# SCH_ThePoweredProject_2023-10-22.net
KiCad netlist of a schematic drawn in EasyEDA
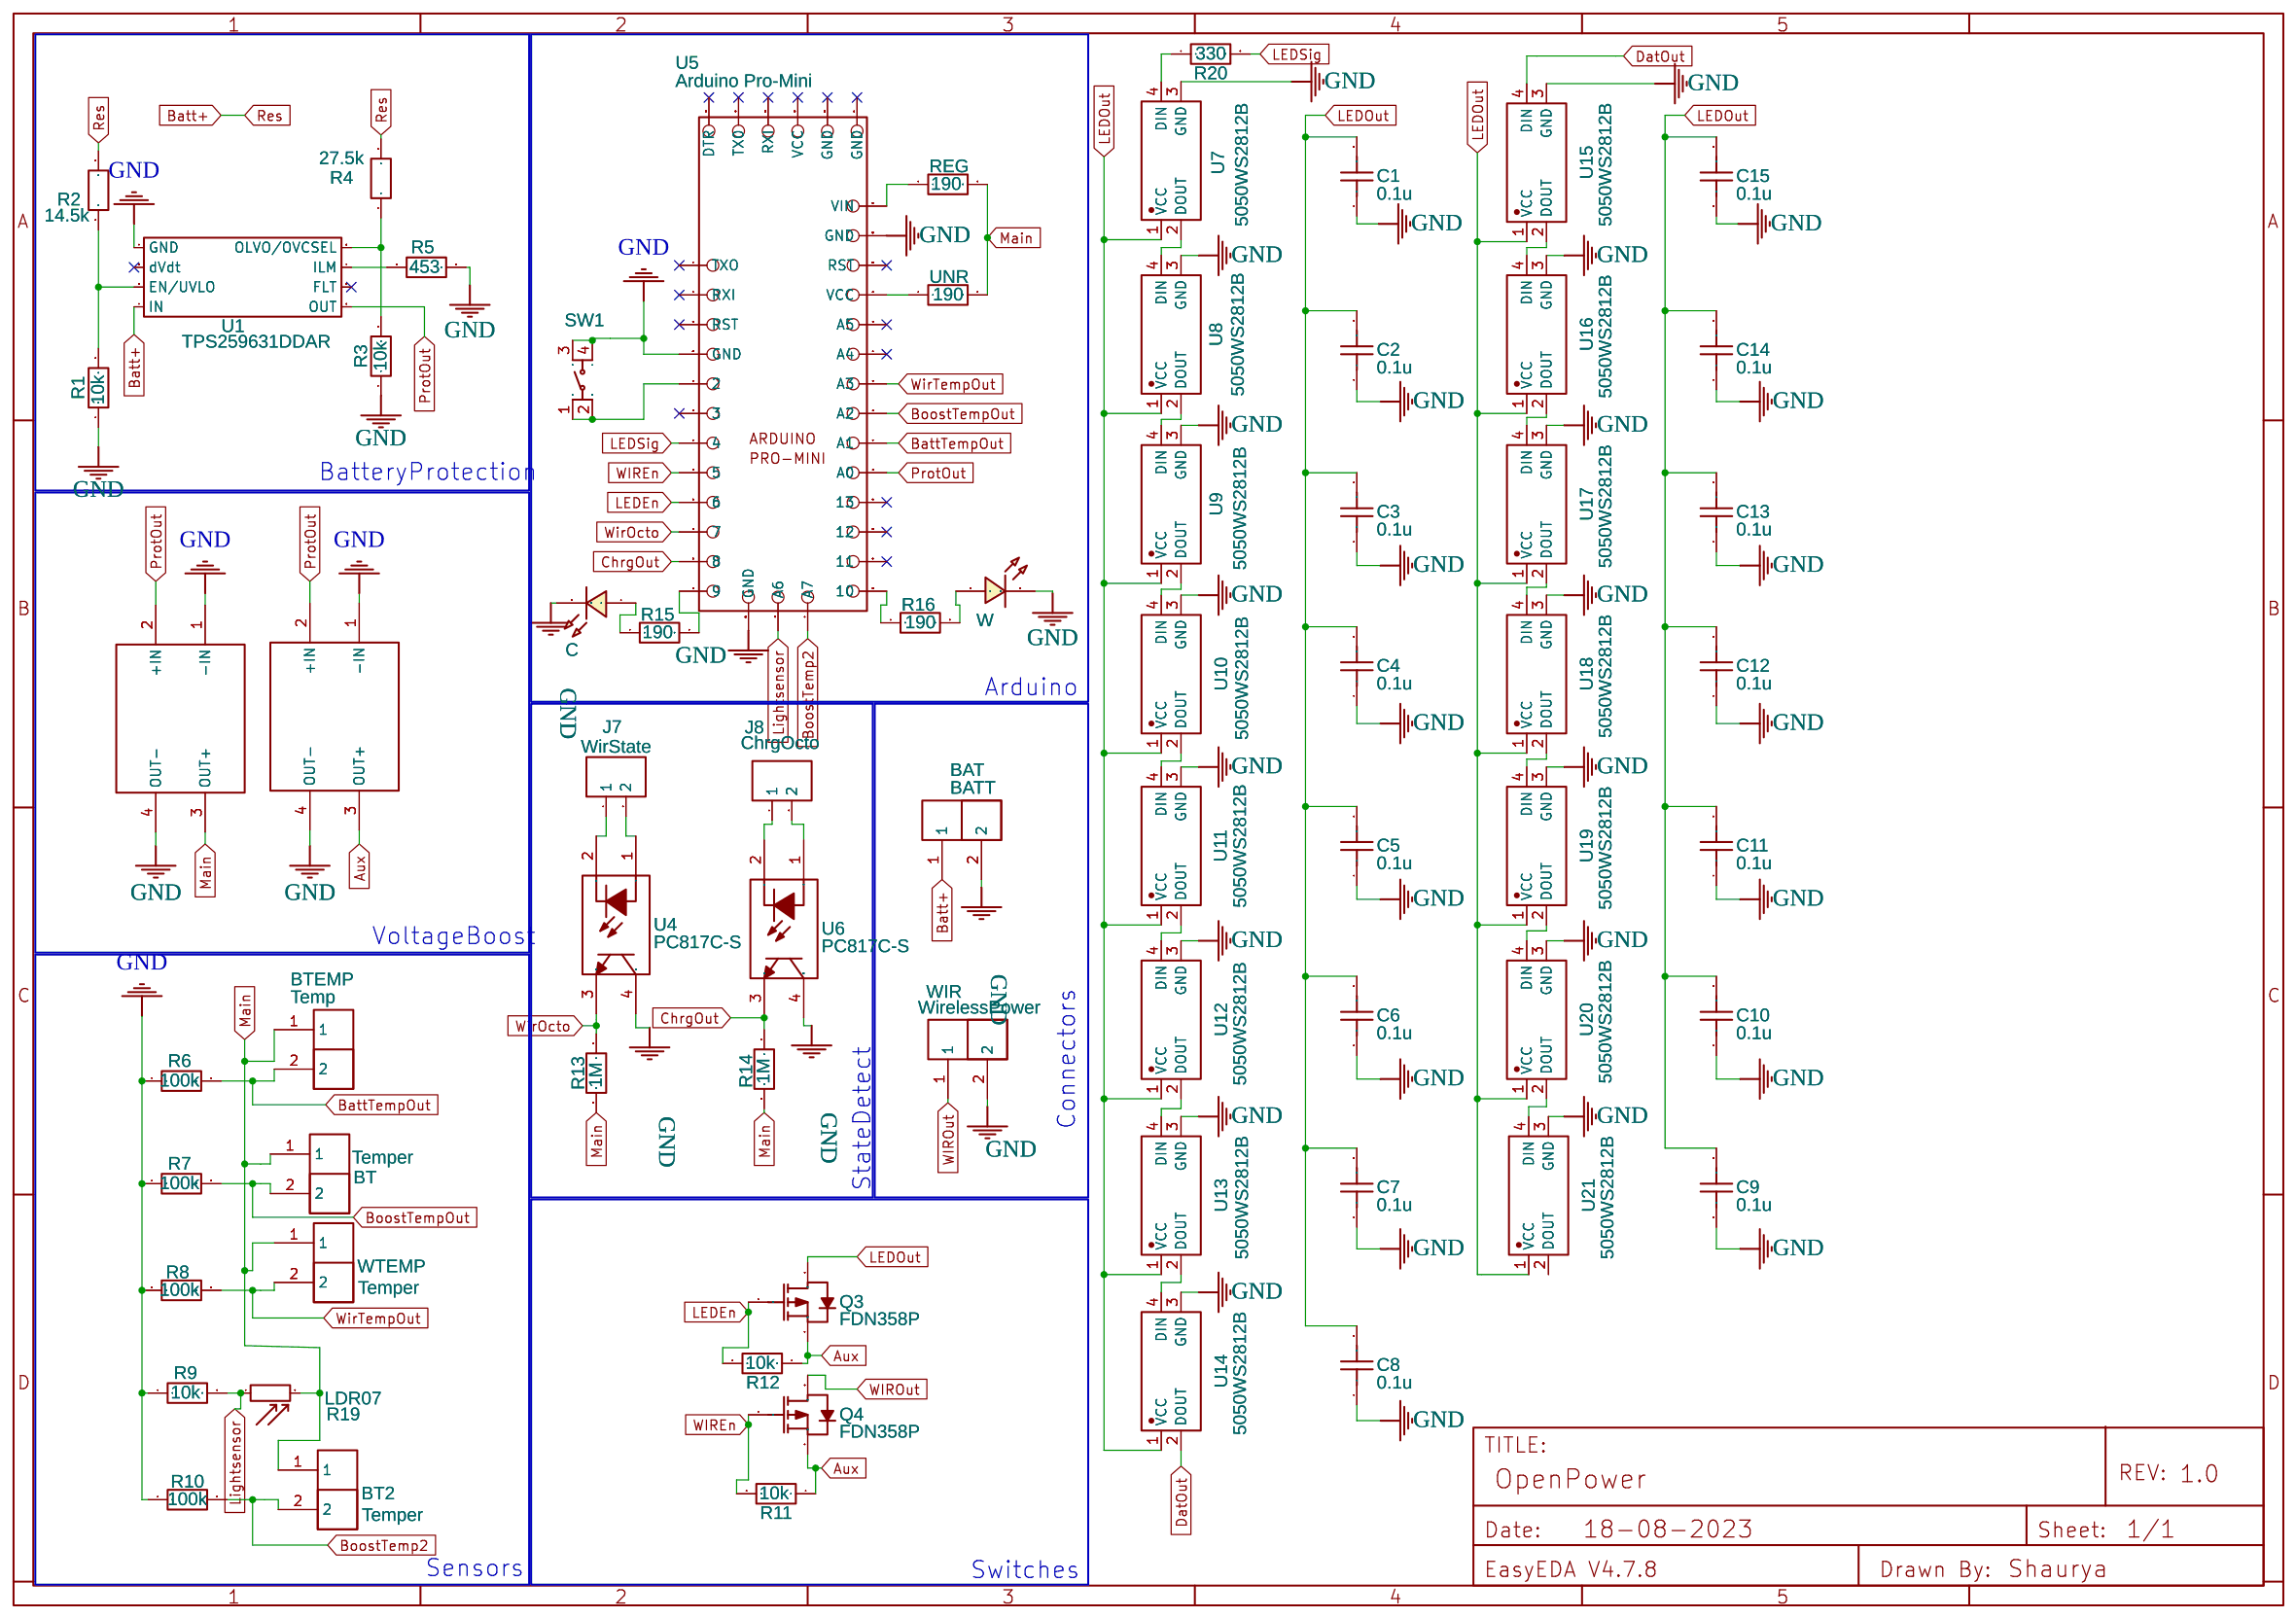
[diagram p0: schematic sheet]

(export (version "E")
  (design (tool "Eeschema 10.0.6"))
  (components
    (comp (ref "BAT") (value "BATT") (libsource (lib "") (part "2 smd pads")))
    (comp (ref "BT") (value "Temper") (libsource (lib "") (part "2 smd pads_4")))
    (comp (ref "BT2") (value "Temper") (libsource (lib "") (part "2 smd pads_4")))
    (comp (ref "BTEMP") (value "Temp") (libsource (lib "") (part "2 smd pads_1")))
    (comp (ref "C")
      (value "LED2")
      (fields
        (field (name "Manufacturer Part") "19-217/R6C-AL1M2VY/3T")
        (field (name "Manufacturer") "EVERLIGHT(台湾亿光)")
      )
      (libsource (lib "") (part "LED-0603_R"))
    )
    (comp (ref "C1") (value "0.1u") (libsource (lib "") (part "C_0603_US")))
    (comp (ref "C2") (value "0.1u") (libsource (lib "") (part "C_0603_US")))
    (comp (ref "C3") (value "0.1u") (libsource (lib "") (part "C_0603_US")))
    (comp (ref "C4") (value "0.1u") (libsource (lib "") (part "C_0603_US")))
    (comp (ref "C5") (value "0.1u") (libsource (lib "") (part "C_0603_US")))
    (comp (ref "C6") (value "0.1u") (libsource (lib "") (part "C_0603_US")))
    (comp (ref "C7") (value "0.1u") (libsource (lib "") (part "C_0603_US")))
    (comp (ref "C8") (value "0.1u") (libsource (lib "") (part "C_0603_US")))
    (comp (ref "C9") (value "0.1u") (libsource (lib "") (part "C_0603_US")))
    (comp (ref "C10") (value "0.1u") (libsource (lib "") (part "C_0603_US")))
    (comp (ref "C11") (value "0.1u") (libsource (lib "") (part "C_0603_US")))
    (comp (ref "C12") (value "0.1u") (libsource (lib "") (part "C_0603_US")))
    (comp (ref "C13") (value "0.1u") (libsource (lib "") (part "C_0603_US")))
    (comp (ref "C14") (value "0.1u") (libsource (lib "") (part "C_0603_US")))
    (comp (ref "C15") (value "0.1u") (libsource (lib "") (part "C_0603_US")))
    (comp (ref "J7") (value "WirState") (libsource (lib "") (part "HDR-M-2.54_1x2")))
    (comp (ref "J8") (value "ChrgOcto") (libsource (lib "") (part "HDR-M-2.54_1x2")))
    (comp (ref "Q3")
      (value "FDN358P")
      (fields (field (name "Manufacturer") "onsemi(安森美)"))
      (libsource (lib "") (part "FDN358P"))
    )
    (comp (ref "Q4")
      (value "FDN358P")
      (fields (field (name "Manufacturer") "onsemi(安森美)"))
      (libsource (lib "") (part "FDN358P"))
    )
    (comp (ref "R1") (value "10k") (libsource (lib "") (part "R_0603_EU_4")))
    (comp (ref "R2") (value "14.5k") (libsource (lib "") (part "R_0603_EU_4")))
    (comp (ref "R3") (value "10k") (libsource (lib "") (part "R_0603_EU_4")))
    (comp (ref "R4") (value "27.5k") (libsource (lib "") (part "R_0603_EU_4")))
    (comp (ref "R5") (value "453") (libsource (lib "") (part "R_0603_EU_2")))
    (comp (ref "R6") (value "100k") (libsource (lib "") (part "R_0603_EU_1")))
    (comp (ref "R7") (value "100k") (libsource (lib "") (part "R_0603_EU_1")))
    (comp (ref "R8") (value "100k") (libsource (lib "") (part "R_0603_EU_1")))
    (comp (ref "R9") (value "10k") (libsource (lib "") (part "R_0603_EU_1")))
    (comp (ref "R10") (value "100k") (libsource (lib "") (part "R_0603_EU_1")))
    (comp (ref "R11") (value "10k") (libsource (lib "") (part "R_0603_EU_2")))
    (comp (ref "R12") (value "10k") (libsource (lib "") (part "R_0603_EU_2")))
    (comp (ref "R13") (value "1M") (libsource (lib "") (part "R_0603_EU")))
    (comp (ref "R14") (value "1M") (libsource (lib "") (part "R_0603_EU")))
    (comp (ref "R15") (value "190") (libsource (lib "") (part "R_0603_EU_1")))
    (comp (ref "R16") (value "190") (libsource (lib "") (part "R_0603_EU_1")))
    (comp (ref "R19") (value "LDR07") (libsource (lib "") (part "LDR07")))
    (comp (ref "R20") (value "330") (libsource (lib "") (part "R_0603_EU_1")))
    (comp (ref "REG") (value "190") (libsource (lib "") (part "R_0603_EU_3")))
    (comp (ref "SW1")
      (value "Black SMD switch")
      (fields (field (name "Manufacturer Part") "PTS 647 SM50 SMTR2 LFS") (field (name "Manufacturer") "C&K"))
      (libsource (lib "") (part "Black SMD switch"))
    )
    (comp (ref "U1") (value "TPS259631DDAR") (libsource (lib "") (part "TPS259631DDAR")))
    (comp (ref "U2")
      (value "Mini boost DC-DC converter")
      (libsource (lib "") (part "Mini boost DC-DC converter"))
    )
    (comp (ref "U3")
      (value "Mini boost DC-DC converter")
      (libsource (lib "") (part "Mini boost DC-DC converter"))
    )
    (comp (ref "U4")
      (value "PC817C-S")
      (fields (field (name "Manufacturer") "UMW(广东友台半导体)"))
      (libsource (lib "") (part "PC817C-S"))
    )
    (comp (ref "U5") (value "Arduino Pro-Mini") (libsource (lib "") (part "Arduino Pro-Mini")))
    (comp (ref "U6")
      (value "PC817C-S")
      (fields (field (name "Manufacturer") "UMW(广东友台半导体)"))
      (libsource (lib "") (part "PC817C-S"))
    )
    (comp (ref "U7") (value "5050WS2812B") (libsource (lib "") (part "5050WS2812B")))
    (comp (ref "U8") (value "5050WS2812B") (libsource (lib "") (part "5050WS2812B")))
    (comp (ref "U9") (value "5050WS2812B") (libsource (lib "") (part "5050WS2812B")))
    (comp (ref "U10") (value "5050WS2812B") (libsource (lib "") (part "5050WS2812B")))
    (comp (ref "U11") (value "5050WS2812B") (libsource (lib "") (part "5050WS2812B")))
    (comp (ref "U12") (value "5050WS2812B") (libsource (lib "") (part "5050WS2812B")))
    (comp (ref "U13") (value "5050WS2812B") (libsource (lib "") (part "5050WS2812B")))
    (comp (ref "U14") (value "5050WS2812B") (libsource (lib "") (part "5050WS2812B")))
    (comp (ref "U15") (value "5050WS2812B") (libsource (lib "") (part "5050WS2812B")))
    (comp (ref "U16") (value "5050WS2812B") (libsource (lib "") (part "5050WS2812B")))
    (comp (ref "U17") (value "5050WS2812B") (libsource (lib "") (part "5050WS2812B")))
    (comp (ref "U18") (value "5050WS2812B") (libsource (lib "") (part "5050WS2812B")))
    (comp (ref "U19") (value "5050WS2812B") (libsource (lib "") (part "5050WS2812B")))
    (comp (ref "U20") (value "5050WS2812B") (libsource (lib "") (part "5050WS2812B")))
    (comp (ref "U21") (value "5050WS2812B") (libsource (lib "") (part "5050WS2812B")))
    (comp (ref "UNR") (value "190") (libsource (lib "") (part "R_0603_EU_5")))
    (comp (ref "W")
      (value "Led1")
      (fields
        (field (name "Manufacturer Part") "19-217/R6C-AL1M2VY/3T")
        (field (name "Manufacturer") "EVERLIGHT(台湾亿光)")
      )
      (libsource (lib "") (part "LED-0603_R_1"))
    )
    (comp (ref "WIR") (value "WirelessPower") (libsource (lib "") (part "2 smd pads_2")))
    (comp (ref "WTEMP") (value "Temper") (libsource (lib "") (part "2 smd pads_3")))
  )
  (nets
    (net (code "1") (name "Aux") (class "Default")
      (node (ref "Q3") (pin "2") (pinfunction "S_2") (pintype "unspecified"))
      (node (ref "Q4") (pin "2") (pinfunction "S_2") (pintype "unspecified"))
      (node (ref "R11") (pin "1") (pinfunction "1_1") (pintype "unspecified"))
      (node (ref "R12") (pin "1") (pinfunction "1_1") (pintype "unspecified"))
      (node (ref "U3") (pin "3") (pinfunction "OUT+_3") (pintype "unspecified"))
    )
    (net (code "2") (name "Batt+") (class "Default")
      (node (ref "BAT") (pin "1") (pinfunction "1_1") (pintype "unspecified"))
      (node (ref "R2") (pin "2") (pinfunction "2_2") (pintype "unspecified"))
      (node (ref "R4") (pin "2") (pinfunction "2_2") (pintype "unspecified"))
      (node (ref "U1") (pin "4") (pinfunction "IN_4") (pintype "unspecified"))
    )
    (net (code "3") (name "BattTempOut") (class "Default")
      (node (ref "BTEMP") (pin "2") (pinfunction "2_2") (pintype "unspecified"))
      (node (ref "R6") (pin "2") (pinfunction "2_2") (pintype "unspecified"))
      (node (ref "U5") (pin "A1") (pinfunction "A1_A1") (pintype "unspecified"))
    )
    (net (code "4") (name "BoostTemp2") (class "Default")
      (node (ref "BT2") (pin "2") (pinfunction "2_2") (pintype "unspecified"))
      (node (ref "R10") (pin "2") (pinfunction "2_2") (pintype "unspecified"))
      (node (ref "U5") (pin "A7") (pinfunction "A7_A7") (pintype "unspecified"))
    )
    (net (code "5") (name "BoostTempOut") (class "Default")
      (node (ref "BT") (pin "2") (pinfunction "2_2") (pintype "unspecified"))
      (node (ref "R7") (pin "2") (pinfunction "2_2") (pintype "unspecified"))
      (node (ref "U5") (pin "A2") (pinfunction "A2_A2") (pintype "unspecified"))
    )
    (net (code "6") (name "ChrgOut") (class "Default")
      (node (ref "R14") (pin "1") (pinfunction "1_1") (pintype "unspecified"))
      (node (ref "U5") (pin "D8") (pinfunction "8_D8") (pintype "unspecified"))
      (node (ref "U6") (pin "3") (pinfunction "EM_3") (pintype "unspecified"))
    )
    (net (code "7") (name "DatOut") (class "Default")
      (node (ref "U14") (pin "2") (pinfunction "DOUT_2") (pintype "unspecified"))
      (node (ref "U15") (pin "4") (pinfunction "DIN_4") (pintype "unspecified"))
    )
    (net (code "8") (name "GND") (class "Default")
      (node (ref "BAT") (pin "2") (pinfunction "2_2") (pintype "unspecified"))
      (node (ref "C") (pin "2") (pinfunction "2_2") (pintype "unspecified"))
      (node (ref "C1") (pin "1") (pinfunction "1_1") (pintype "unspecified"))
      (node (ref "C10") (pin "1") (pinfunction "1_1") (pintype "unspecified"))
      (node (ref "C11") (pin "1") (pinfunction "1_1") (pintype "unspecified"))
      (node (ref "C12") (pin "1") (pinfunction "1_1") (pintype "unspecified"))
      (node (ref "C13") (pin "1") (pinfunction "1_1") (pintype "unspecified"))
      (node (ref "C14") (pin "1") (pinfunction "1_1") (pintype "unspecified"))
      (node (ref "C15") (pin "1") (pinfunction "1_1") (pintype "unspecified"))
      (node (ref "C2") (pin "1") (pinfunction "1_1") (pintype "unspecified"))
      (node (ref "C3") (pin "1") (pinfunction "1_1") (pintype "unspecified"))
      (node (ref "C4") (pin "1") (pinfunction "1_1") (pintype "unspecified"))
      (node (ref "C5") (pin "1") (pinfunction "1_1") (pintype "unspecified"))
      (node (ref "C6") (pin "1") (pinfunction "1_1") (pintype "unspecified"))
      (node (ref "C7") (pin "1") (pinfunction "1_1") (pintype "unspecified"))
      (node (ref "C8") (pin "1") (pinfunction "1_1") (pintype "unspecified"))
      (node (ref "C9") (pin "1") (pinfunction "1_1") (pintype "unspecified"))
      (node (ref "R1") (pin "1") (pinfunction "1_1") (pintype "unspecified"))
      (node (ref "R10") (pin "1") (pinfunction "1_1") (pintype "unspecified"))
      (node (ref "R3") (pin "1") (pinfunction "1_1") (pintype "unspecified"))
      (node (ref "R5") (pin "1") (pinfunction "1_1") (pintype "unspecified"))
      (node (ref "R6") (pin "1") (pinfunction "1_1") (pintype "unspecified"))
      (node (ref "R7") (pin "1") (pinfunction "1_1") (pintype "unspecified"))
      (node (ref "R8") (pin "1") (pinfunction "1_1") (pintype "unspecified"))
      (node (ref "R9") (pin "1") (pinfunction "1_1") (pintype "unspecified"))
      (node (ref "SW1") (pin "3") (pinfunction "3_3") (pintype "unspecified"))
      (node (ref "SW1") (pin "4") (pinfunction "4_4") (pintype "unspecified"))
      (node (ref "U1") (pin "1") (pinfunction "GND_1") (pintype "unspecified"))
      (node (ref "U10") (pin "3") (pinfunction "GND_3") (pintype "unspecified"))
      (node (ref "U11") (pin "3") (pinfunction "GND_3") (pintype "unspecified"))
      (node (ref "U12") (pin "3") (pinfunction "GND_3") (pintype "unspecified"))
      (node (ref "U13") (pin "3") (pinfunction "GND_3") (pintype "unspecified"))
      (node (ref "U14") (pin "3") (pinfunction "GND_3") (pintype "unspecified"))
      (node (ref "U15") (pin "3") (pinfunction "GND_3") (pintype "unspecified"))
      (node (ref "U16") (pin "3") (pinfunction "GND_3") (pintype "unspecified"))
      (node (ref "U17") (pin "3") (pinfunction "GND_3") (pintype "unspecified"))
      (node (ref "U18") (pin "3") (pinfunction "GND_3") (pintype "unspecified"))
      (node (ref "U19") (pin "3") (pinfunction "GND_3") (pintype "unspecified"))
      (node (ref "U2") (pin "1") (pinfunction "-IN_1") (pintype "unspecified"))
      (node (ref "U2") (pin "4") (pinfunction "OUT-_4") (pintype "unspecified"))
      (node (ref "U20") (pin "3") (pinfunction "GND_3") (pintype "unspecified"))
      (node (ref "U21") (pin "3") (pinfunction "GND_3") (pintype "unspecified"))
      (node (ref "U3") (pin "1") (pinfunction "-IN_1") (pintype "unspecified"))
      (node (ref "U3") (pin "4") (pinfunction "OUT-_4") (pintype "unspecified"))
      (node (ref "U4") (pin "4") (pinfunction "COL_4") (pintype "unspecified"))
      (node (ref "U5") (pin "GND") (pinfunction "GND_GND") (pintype "unspecified"))
      (node (ref "U5") (pin "GND@1") (pinfunction "GND_GND@1") (pintype "unspecified"))
      (node (ref "U5") (pin "GND@3") (pinfunction "GND_GND@3") (pintype "unspecified"))
      (node (ref "U6") (pin "4") (pinfunction "COL_4") (pintype "unspecified"))
      (node (ref "U7") (pin "3") (pinfunction "GND_3") (pintype "unspecified"))
      (node (ref "U8") (pin "3") (pinfunction "GND_3") (pintype "unspecified"))
      (node (ref "U9") (pin "3") (pinfunction "GND_3") (pintype "unspecified"))
      (node (ref "W") (pin "2") (pinfunction "2_2") (pintype "unspecified"))
      (node (ref "WIR") (pin "2") (pinfunction "2_2") (pintype "unspecified"))
    )
    (net (code "9") (name "LEDEn") (class "Default")
      (node (ref "Q3") (pin "1") (pinfunction "G_1") (pintype "unspecified"))
      (node (ref "R12") (pin "2") (pinfunction "2_2") (pintype "unspecified"))
      (node (ref "U5") (pin "D6") (pinfunction "6_D6") (pintype "unspecified"))
    )
    (net (code "10") (name "LEDOut") (class "Default")
      (node (ref "C1") (pin "2") (pinfunction "2_2") (pintype "unspecified"))
      (node (ref "C10") (pin "2") (pinfunction "2_2") (pintype "unspecified"))
      (node (ref "C11") (pin "2") (pinfunction "2_2") (pintype "unspecified"))
      (node (ref "C12") (pin "2") (pinfunction "2_2") (pintype "unspecified"))
      (node (ref "C13") (pin "2") (pinfunction "2_2") (pintype "unspecified"))
      (node (ref "C14") (pin "2") (pinfunction "2_2") (pintype "unspecified"))
      (node (ref "C15") (pin "2") (pinfunction "2_2") (pintype "unspecified"))
      (node (ref "C2") (pin "2") (pinfunction "2_2") (pintype "unspecified"))
      (node (ref "C3") (pin "2") (pinfunction "2_2") (pintype "unspecified"))
      (node (ref "C4") (pin "2") (pinfunction "2_2") (pintype "unspecified"))
      (node (ref "C5") (pin "2") (pinfunction "2_2") (pintype "unspecified"))
      (node (ref "C6") (pin "2") (pinfunction "2_2") (pintype "unspecified"))
      (node (ref "C7") (pin "2") (pinfunction "2_2") (pintype "unspecified"))
      (node (ref "C8") (pin "2") (pinfunction "2_2") (pintype "unspecified"))
      (node (ref "C9") (pin "2") (pinfunction "2_2") (pintype "unspecified"))
      (node (ref "Q3") (pin "3") (pinfunction "D_3") (pintype "unspecified"))
      (node (ref "U10") (pin "1") (pinfunction "VCC_1") (pintype "unspecified"))
      (node (ref "U11") (pin "1") (pinfunction "VCC_1") (pintype "unspecified"))
      (node (ref "U12") (pin "1") (pinfunction "VCC_1") (pintype "unspecified"))
      (node (ref "U13") (pin "1") (pinfunction "VCC_1") (pintype "unspecified"))
      (node (ref "U14") (pin "1") (pinfunction "VCC_1") (pintype "unspecified"))
      (node (ref "U15") (pin "1") (pinfunction "VCC_1") (pintype "unspecified"))
      (node (ref "U16") (pin "1") (pinfunction "VCC_1") (pintype "unspecified"))
      (node (ref "U17") (pin "1") (pinfunction "VCC_1") (pintype "unspecified"))
      (node (ref "U18") (pin "1") (pinfunction "VCC_1") (pintype "unspecified"))
      (node (ref "U19") (pin "1") (pinfunction "VCC_1") (pintype "unspecified"))
      (node (ref "U20") (pin "1") (pinfunction "VCC_1") (pintype "unspecified"))
      (node (ref "U21") (pin "1") (pinfunction "VCC_1") (pintype "unspecified"))
      (node (ref "U7") (pin "1") (pinfunction "VCC_1") (pintype "unspecified"))
      (node (ref "U8") (pin "1") (pinfunction "VCC_1") (pintype "unspecified"))
      (node (ref "U9") (pin "1") (pinfunction "VCC_1") (pintype "unspecified"))
    )
    (net (code "11") (name "LEDSig") (class "Default")
      (node (ref "R20") (pin "2") (pinfunction "2_2") (pintype "unspecified"))
      (node (ref "U5") (pin "D4") (pinfunction "4_D4") (pintype "unspecified"))
    )
    (net (code "12") (name "Lightsensor") (class "Default")
      (node (ref "R19") (pin "1") (pintype "unspecified"))
      (node (ref "R9") (pin "2") (pinfunction "2_2") (pintype "unspecified"))
      (node (ref "U5") (pin "A6") (pinfunction "A6_A6") (pintype "unspecified"))
    )
    (net (code "13") (name "Main") (class "Default")
      (node (ref "BT") (pin "1") (pinfunction "1_1") (pintype "unspecified"))
      (node (ref "BT2") (pin "1") (pinfunction "1_1") (pintype "unspecified"))
      (node (ref "BTEMP") (pin "1") (pinfunction "1_1") (pintype "unspecified"))
      (node (ref "R13") (pin "2") (pinfunction "2_2") (pintype "unspecified"))
      (node (ref "R14") (pin "2") (pinfunction "2_2") (pintype "unspecified"))
      (node (ref "R19") (pin "2") (pintype "unspecified"))
      (node (ref "REG") (pin "2") (pinfunction "2_2") (pintype "unspecified"))
      (node (ref "U2") (pin "3") (pinfunction "OUT+_3") (pintype "unspecified"))
      (node (ref "UNR") (pin "2") (pinfunction "2_2") (pintype "unspecified"))
      (node (ref "WTEMP") (pin "1") (pinfunction "1_1") (pintype "unspecified"))
    )
    (net (code "14") (name "Net-(C-Pad1)") (class "Default")
      (node (ref "C") (pin "1") (pinfunction "1_1") (pintype "unspecified"))
      (node (ref "R15") (pin "1") (pinfunction "1_1") (pintype "unspecified"))
    )
    (net (code "15") (name "Net-(R16-Pad2)") (class "Default")
      (node (ref "R16") (pin "2") (pinfunction "2_2") (pintype "unspecified"))
      (node (ref "W") (pin "1") (pinfunction "1_1") (pintype "unspecified"))
    )
    (net (code "16") (name "Net-(U1-EN{slash}UVLO)") (class "Default")
      (node (ref "R1") (pin "2") (pinfunction "2_2") (pintype "unspecified"))
      (node (ref "R2") (pin "1") (pinfunction "1_1") (pintype "unspecified"))
      (node (ref "U1") (pin "3") (pinfunction "EN/UVLO_3") (pintype "unspecified"))
    )
    (net (code "17") (name "Net-(U1-ILM)") (class "Default")
      (node (ref "R5") (pin "2") (pinfunction "2_2") (pintype "unspecified"))
      (node (ref "U1") (pin "7") (pinfunction "ILM_7") (pintype "unspecified"))
    )
    (net (code "18") (name "Net-(U1-OLVO{slash}OVCSEL)") (class "Default")
      (node (ref "R3") (pin "2") (pinfunction "2_2") (pintype "unspecified"))
      (node (ref "R4") (pin "1") (pinfunction "1_1") (pintype "unspecified"))
      (node (ref "U1") (pin "8") (pinfunction "OLVO/OVCSEL_8") (pintype "unspecified"))
    )
    (net (code "19") (name "Net-(U4-AN)") (class "Default")
      (node (ref "J7") (pin "2") (pinfunction "2_2") (pintype "unspecified"))
      (node (ref "U4") (pin "1") (pinfunction "AN_1") (pintype "unspecified"))
    )
    (net (code "20") (name "Net-(U4-CAT)") (class "Default")
      (node (ref "J7") (pin "1") (pinfunction "1_1") (pintype "unspecified"))
      (node (ref "U4") (pin "2") (pinfunction "CAT_2") (pintype "unspecified"))
    )
    (net (code "21") (name "Net-(U5-2)") (class "Default")
      (node (ref "SW1") (pin "1") (pinfunction "1_1") (pintype "unspecified"))
      (node (ref "SW1") (pin "2") (pinfunction "2_2") (pintype "unspecified"))
      (node (ref "U5") (pin "D2") (pinfunction "2_D2") (pintype "unspecified"))
    )
    (net (code "22") (name "Net-(U5-9)") (class "Default")
      (node (ref "R15") (pin "2") (pinfunction "2_2") (pintype "unspecified"))
      (node (ref "U5") (pin "D9") (pinfunction "9_D9") (pintype "unspecified"))
    )
    (net (code "23") (name "Net-(U5-10)") (class "Default")
      (node (ref "R16") (pin "1") (pinfunction "1_1") (pintype "unspecified"))
      (node (ref "U5") (pin "D10") (pinfunction "10_D10") (pintype "unspecified"))
    )
    (net (code "24") (name "Net-(U5-PadVCC)") (class "Default")
      (node (ref "U5") (pin "VCC") (pinfunction "VCC_VCC") (pintype "unspecified"))
      (node (ref "UNR") (pin "1") (pinfunction "1_1") (pintype "unspecified"))
    )
    (net (code "25") (name "Net-(U5-VIN)") (class "Default")
      (node (ref "REG") (pin "1") (pinfunction "1_1") (pintype "unspecified"))
      (node (ref "U5") (pin "RAW") (pinfunction "VIN_RAW") (pintype "unspecified"))
    )
    (net (code "26") (name "Net-(U6-AN)") (class "Default")
      (node (ref "J8") (pin "2") (pinfunction "2_2") (pintype "unspecified"))
      (node (ref "U6") (pin "1") (pinfunction "AN_1") (pintype "unspecified"))
    )
    (net (code "27") (name "Net-(U6-CAT)") (class "Default")
      (node (ref "J8") (pin "1") (pinfunction "1_1") (pintype "unspecified"))
      (node (ref "U6") (pin "2") (pinfunction "CAT_2") (pintype "unspecified"))
    )
    (net (code "28") (name "Net-(U7-DIN)") (class "Default")
      (node (ref "R20") (pin "1") (pinfunction "1_1") (pintype "unspecified"))
      (node (ref "U7") (pin "4") (pinfunction "DIN_4") (pintype "unspecified"))
    )
    (net (code "29") (name "Net-(U7-DOUT)") (class "Default")
      (node (ref "U7") (pin "2") (pinfunction "DOUT_2") (pintype "unspecified"))
      (node (ref "U8") (pin "4") (pinfunction "DIN_4") (pintype "unspecified"))
    )
    (net (code "30") (name "Net-(U8-DOUT)") (class "Default")
      (node (ref "U8") (pin "2") (pinfunction "DOUT_2") (pintype "unspecified"))
      (node (ref "U9") (pin "4") (pinfunction "DIN_4") (pintype "unspecified"))
    )
    (net (code "31") (name "Net-(U10-DIN)") (class "Default")
      (node (ref "U10") (pin "4") (pinfunction "DIN_4") (pintype "unspecified"))
      (node (ref "U9") (pin "2") (pinfunction "DOUT_2") (pintype "unspecified"))
    )
    (net (code "32") (name "Net-(U10-DOUT)") (class "Default")
      (node (ref "U10") (pin "2") (pinfunction "DOUT_2") (pintype "unspecified"))
      (node (ref "U11") (pin "4") (pinfunction "DIN_4") (pintype "unspecified"))
    )
    (net (code "33") (name "Net-(U11-DOUT)") (class "Default")
      (node (ref "U11") (pin "2") (pinfunction "DOUT_2") (pintype "unspecified"))
      (node (ref "U12") (pin "4") (pinfunction "DIN_4") (pintype "unspecified"))
    )
    (net (code "34") (name "Net-(U12-DOUT)") (class "Default")
      (node (ref "U12") (pin "2") (pinfunction "DOUT_2") (pintype "unspecified"))
      (node (ref "U13") (pin "4") (pinfunction "DIN_4") (pintype "unspecified"))
    )
    (net (code "35") (name "Net-(U13-DOUT)") (class "Default")
      (node (ref "U13") (pin "2") (pinfunction "DOUT_2") (pintype "unspecified"))
      (node (ref "U14") (pin "4") (pinfunction "DIN_4") (pintype "unspecified"))
    )
    (net (code "36") (name "Net-(U15-DOUT)") (class "Default")
      (node (ref "U15") (pin "2") (pinfunction "DOUT_2") (pintype "unspecified"))
      (node (ref "U16") (pin "4") (pinfunction "DIN_4") (pintype "unspecified"))
    )
    (net (code "37") (name "Net-(U16-DOUT)") (class "Default")
      (node (ref "U16") (pin "2") (pinfunction "DOUT_2") (pintype "unspecified"))
      (node (ref "U17") (pin "4") (pinfunction "DIN_4") (pintype "unspecified"))
    )
    (net (code "38") (name "Net-(U17-DOUT)") (class "Default")
      (node (ref "U17") (pin "2") (pinfunction "DOUT_2") (pintype "unspecified"))
      (node (ref "U18") (pin "4") (pinfunction "DIN_4") (pintype "unspecified"))
    )
    (net (code "39") (name "Net-(U18-DOUT)") (class "Default")
      (node (ref "U18") (pin "2") (pinfunction "DOUT_2") (pintype "unspecified"))
      (node (ref "U19") (pin "4") (pinfunction "DIN_4") (pintype "unspecified"))
    )
    (net (code "40") (name "Net-(U19-DOUT)") (class "Default")
      (node (ref "U19") (pin "2") (pinfunction "DOUT_2") (pintype "unspecified"))
      (node (ref "U20") (pin "4") (pinfunction "DIN_4") (pintype "unspecified"))
    )
    (net (code "41") (name "Net-(U20-DOUT)") (class "Default")
      (node (ref "U20") (pin "2") (pinfunction "DOUT_2") (pintype "unspecified"))
      (node (ref "U21") (pin "4") (pinfunction "DIN_4") (pintype "unspecified"))
    )
    (net (code "42") (name "ProtOut") (class "Default")
      (node (ref "U1") (pin "5") (pinfunction "OUT_5") (pintype "unspecified"))
      (node (ref "U2") (pin "2") (pinfunction "+IN_2") (pintype "unspecified"))
      (node (ref "U3") (pin "2") (pinfunction "+IN_2") (pintype "unspecified"))
      (node (ref "U5") (pin "A0") (pinfunction "A0_A0") (pintype "unspecified"))
    )
    (net (code "43") (name "WIREn") (class "Default")
      (node (ref "Q4") (pin "1") (pinfunction "G_1") (pintype "unspecified"))
      (node (ref "R11") (pin "2") (pinfunction "2_2") (pintype "unspecified"))
      (node (ref "U5") (pin "D5") (pinfunction "5_D5") (pintype "unspecified"))
    )
    (net (code "44") (name "WIROut") (class "Default")
      (node (ref "Q4") (pin "3") (pinfunction "D_3") (pintype "unspecified"))
      (node (ref "WIR") (pin "1") (pinfunction "1_1") (pintype "unspecified"))
    )
    (net (code "45") (name "WirOcto") (class "Default")
      (node (ref "R13") (pin "1") (pinfunction "1_1") (pintype "unspecified"))
      (node (ref "U4") (pin "3") (pinfunction "EM_3") (pintype "unspecified"))
      (node (ref "U5") (pin "D7") (pinfunction "7_D7") (pintype "unspecified"))
    )
    (net (code "46") (name "WirTempOut") (class "Default")
      (node (ref "R8") (pin "2") (pinfunction "2_2") (pintype "unspecified"))
      (node (ref "U5") (pin "A3") (pinfunction "A3_A3") (pintype "unspecified"))
      (node (ref "WTEMP") (pin "2") (pinfunction "2_2") (pintype "unspecified"))
    )
    (net (code "47") (name "unconnected-(U1-FLT-Pad6)") (class "Default")
      (node (ref "U1") (pin "6") (pinfunction "FLT_6") (pintype "unspecified+no_connect"))
    )
    (net (code "48") (name "unconnected-(U1-dVdt-Pad2)") (class "Default")
      (node (ref "U1") (pin "2") (pinfunction "dVdt_2") (pintype "unspecified+no_connect"))
    )
    (net (code "49") (name "unconnected-(U5-3-PadD3)") (class "Default")
      (node (ref "U5") (pin "D3") (pinfunction "3_D3") (pintype "unspecified+no_connect"))
    )
    (net (code "50") (name "unconnected-(U5-11-PadD11)") (class "Default")
      (node (ref "U5") (pin "D11") (pinfunction "11_D11") (pintype "unspecified+no_connect"))
    )
    (net (code "51") (name "unconnected-(U5-12-PadD12)") (class "Default")
      (node (ref "U5") (pin "D12") (pinfunction "12_D12") (pintype "unspecified+no_connect"))
    )
    (net (code "52") (name "unconnected-(U5-13-PadD13)") (class "Default")
      (node (ref "U5") (pin "D13") (pinfunction "13_D13") (pintype "unspecified+no_connect"))
    )
    (net (code "53") (name "unconnected-(U5-GND-PadBLK)") (class "Default")
      (node (ref "U5") (pin "BLK") (pinfunction "GND_BLK") (pintype "unspecified+no_connect"))
    )
    (net (code "54") (name "unconnected-(U5-GND-PadGND@2)") (class "Default")
      (node (ref "U5") (pin "GND@2") (pinfunction "GND_GND@2") (pintype "unspecified+no_connect"))
    )
    (net (code "55") (name "unconnected-(U5-PadA4)") (class "Default")
      (node (ref "U5") (pin "A4") (pinfunction "A4_A4") (pintype "unspecified+no_connect"))
    )
    (net (code "56") (name "unconnected-(U5-PadA5)") (class "Default")
      (node (ref "U5") (pin "A5") (pinfunction "A5_A5") (pintype "unspecified+no_connect"))
    )
    (net (code "57") (name "unconnected-(U5-PadDTR)") (class "Default")
      (node (ref "U5") (pin "DTR") (pinfunction "DTR_DTR") (pintype "unspecified+no_connect"))
    )
    (net (code "58") (name "unconnected-(U5-PadRST)") (class "Default")
      (node (ref "U5") (pin "RST") (pinfunction "RST_RST") (pintype "unspecified+no_connect"))
    )
    (net (code "59") (name "unconnected-(U5-RST-PadRST@1)") (class "Default")
      (node (ref "U5") (pin "RST@1") (pinfunction "RST_RST@1") (pintype "unspecified+no_connect"))
    )
    (net (code "60") (name "unconnected-(U5-RXI-PadRX)") (class "Default")
      (node (ref "U5") (pin "RX") (pinfunction "RXI_RX") (pintype "unspecified+no_connect"))
    )
    (net (code "61") (name "unconnected-(U5-RXI-PadRX@1)") (class "Default")
      (node (ref "U5") (pin "RX@1") (pinfunction "RXI_RX@1") (pintype "unspecified+no_connect"))
    )
    (net (code "62") (name "unconnected-(U5-TX0-PadTX@1)") (class "Default")
      (node (ref "U5") (pin "TX@1") (pinfunction "TX0_TX@1") (pintype "unspecified+no_connect"))
    )
    (net (code "63") (name "unconnected-(U5-TXO-PadTX)") (class "Default")
      (node (ref "U5") (pin "TX") (pinfunction "TXO_TX") (pintype "unspecified+no_connect"))
    )
    (net (code "64") (name "unconnected-(U5-VCC-PadVCC@1)") (class "Default")
      (node (ref "U5") (pin "VCC@1") (pinfunction "VCC_VCC@1") (pintype "unspecified+no_connect"))
    )
    (net (code "65") (name "unconnected-(U21-DOUT-Pad2)") (class "Default")
      (node (ref "U21") (pin "2") (pinfunction "DOUT_2") (pintype "unspecified"))
    )
  )
)
